# PARK_COUNTER_PT1_1.net
KiCad netlist of a schematic drawn in Altium Designer
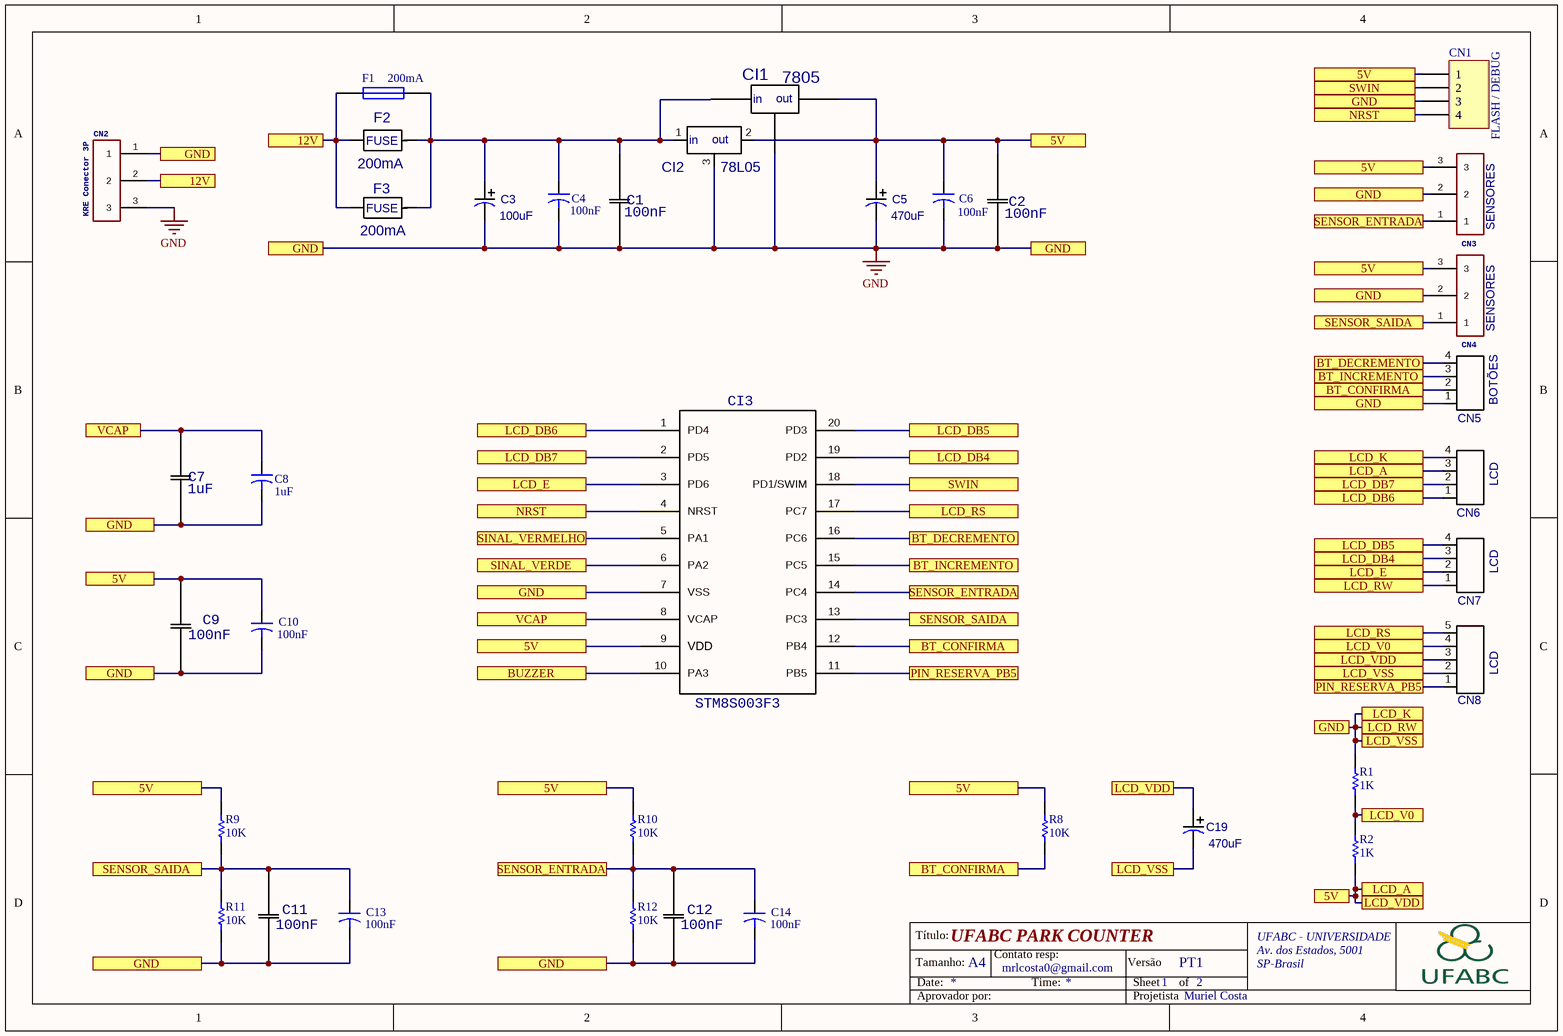
[diagram p0: PARK_COUNTER_PT1_1.SchDoc]

(export (version "E")
  (design (tool "Eeschema 10.0.6"))
  (components
    (comp (ref "C1")
      (value "100nF")
      (footprint "C0603")
      (description "Capacitor")
      (fields (field (name "Comment") "C0603"))
      (libsource (lib "SMD") (part "C0603"))
    )
    (comp (ref "C2")
      (value "100nF")
      (footprint "C0603")
      (description "Capacitor")
      (fields (field (name "Comment") "C0603"))
      (libsource (lib "SMD") (part "C0603"))
    )
    (comp (ref "C3")
      (value "100uF")
      (footprint "C_ELET_D8P5/3.5")
      (fields (field (name "Comment") "C_ELET_D8P5_35"))
      (libsource (lib "PTH") (part "C_ELET_D8P5_35"))
    )
    (comp (ref "C4")
      (value "100nF")
      (footprint "CAPR5-4X5")
      (description "Capacitor")
      (fields (field (name "Comment") "Cap2") (field (name "PUBLISHER") "Altium Limited"))
      (libsource (lib "Miscellaneous Devices") (part "Cap2"))
    )
    (comp (ref "C5")
      (value "470uF")
      (footprint "C_ELET_D8P5/3.5")
      (fields (field (name "Comment") "C_ELET_D8P5_35"))
      (libsource (lib "PTH") (part "C_ELET_D8P5_35"))
    )
    (comp (ref "C6")
      (value "100nF")
      (footprint "CAPR5-4X5")
      (description "Capacitor")
      (fields (field (name "Comment") "Cap2") (field (name "PUBLISHER") "Altium Limited"))
      (libsource (lib "Miscellaneous Devices") (part "Cap2"))
    )
    (comp (ref "C7")
      (value "1uF")
      (footprint "C0603")
      (description "Capacitor")
      (fields (field (name "Comment") "C0603"))
      (libsource (lib "SMD") (part "C0603"))
    )
    (comp (ref "C8")
      (value "1uF")
      (footprint "CAPR5-4X5")
      (description "Capacitor")
      (fields (field (name "Comment") "Cap2") (field (name "PUBLISHER") "Altium Limited"))
      (libsource (lib "Miscellaneous Devices") (part "Cap2"))
    )
    (comp (ref "C9")
      (value "100nF")
      (footprint "C0603")
      (description "Capacitor")
      (fields (field (name "Comment") "C0603"))
      (libsource (lib "SMD") (part "C0603"))
    )
    (comp (ref "C10")
      (value "100nF")
      (footprint "CAPR5-4X5")
      (description "Capacitor")
      (fields (field (name "Comment") "Cap2") (field (name "PUBLISHER") "Altium Limited"))
      (libsource (lib "Miscellaneous Devices") (part "Cap2"))
    )
    (comp (ref "C11")
      (value "100nF")
      (footprint "C0603")
      (description "Capacitor")
      (fields (field (name "Comment") "C0603"))
      (libsource (lib "SMD") (part "C0603"))
    )
    (comp (ref "C12")
      (value "100nF")
      (footprint "C0603")
      (description "Capacitor")
      (fields (field (name "Comment") "C0603"))
      (libsource (lib "SMD") (part "C0603"))
    )
    (comp (ref "C13")
      (value "100nF")
      (footprint "CAPR5-4X5")
      (description "Capacitor")
      (fields (field (name "Comment") "Cap2") (field (name "PUBLISHER") "Altium Limited"))
      (libsource (lib "Miscellaneous Devices") (part "Cap2"))
    )
    (comp (ref "C14")
      (value "100nF")
      (footprint "CAPR5-4X5")
      (description "Capacitor")
      (fields (field (name "Comment") "Cap2") (field (name "PUBLISHER") "Altium Limited"))
      (libsource (lib "Miscellaneous Devices") (part "Cap2"))
    )
    (comp (ref "C19")
      (value "470uF")
      (footprint "C_ELET_D8P5/3.5")
      (fields (field (name "Comment") "C_ELET_D8P5_35"))
      (libsource (lib "PTH") (part "C_ELET_D8P5_35"))
    )
    (comp (ref "CI1")
      (value "7805")
      (footprint "CI_7805_TO220_V")
      (fields (field (name "PART NUMBER") "004.02.00002"))
      (libsource (lib "PTH") (part "CI_7805_TO220_V"))
    )
    (comp (ref "CI2")
      (value "78L05")
      (footprint "TO92_78L05")
      (description "Glass Zener Diode, 500 Milliwatt")
      (fields (field (name "PART NUMBER") "004.02.00003"))
      (libsource (lib "PTH") (part "CI_78L05_TO92"))
    )
    (comp (ref "CI3")
      (value "STM8S003F3")
      (footprint "TSSOP20")
      (fields (field (name "PART NUMBER") "004.07.00026") (field (name "Comment") "CI_STM8S003F3_TSSOP20"))
      (libsource (lib "SMD") (part "CI_STM8S003F3_TSSOP20"))
    )
    (comp (ref "CN1")
      (value "FLASH / DEBUG")
      (footprint "HDR1X4")
      (description "Header, 4-Pin")
      (fields (field (name "PUBLISHER") "Altium Limited"))
      (libsource (lib "Miscellaneous Connectors") (part "Header 4"))
    )
    (comp (ref "CN2") (value "KRE Conector 3P") (footprint "KRE-3P") (libsource (lib "kre") (part "KRE-3P")))
    (comp (ref "CN3") (value "SENSORES") (footprint "KRE-3P") (libsource (lib "kre") (part "KRE-3P")))
    (comp (ref "CN4") (value "SENSORES") (footprint "KRE-3P") (libsource (lib "kre") (part "KRE-3P")))
    (comp (ref "CN5")
      (value "BOTÕES")
      (footprint "CON_BP1X4_180")
      (description "Capacitor")
      (fields (field (name "Comment") "CON_BP1X4_180"))
      (libsource (lib "CONECTORES") (part "CON_BP1X4_180"))
    )
    (comp (ref "CN6")
      (value "LCD")
      (footprint "CON_BP1X4_180")
      (description "Capacitor")
      (fields (field (name "Comment") "CON_BP1X4_180"))
      (libsource (lib "CONECTORES") (part "CON_BP1X4_180"))
    )
    (comp (ref "CN7")
      (value "LCD")
      (footprint "CON_BP1X4_180")
      (description "Capacitor")
      (fields (field (name "Comment") "CON_BP1X4_180"))
      (libsource (lib "CONECTORES") (part "CON_BP1X4_180"))
    )
    (comp (ref "CN8")
      (value "LCD")
      (footprint "CON_BP1X5_180")
      (fields (field (name "Comment") "CON_BP1X5_180"))
      (libsource (lib "CONECTORES") (part "CON_BP1X5_180"))
    )
    (comp (ref "F1")
      (value "200mA")
      (footprint "PIN-W2/E2.8")
      (description "Fuse")
      (fields (field (name "PUBLISHER") "Altium Limited"))
      (libsource (lib "Miscellaneous Devices") (part "Fuse 1"))
    )
    (comp (ref "F2")
      (value "200mA")
      (footprint "MINI_FUSE_BOARD_GLASS")
      (fields (field (name "Comment") "MINI_FUSE_BOARD_GLASS"))
      (libsource (lib "PTH") (part "fuse_board_glass"))
    )
    (comp (ref "F3")
      (value "200mA")
      (footprint "fuse_board_suporte")
      (fields (field (name "Comment") "MINI_FUSE_BOARD_SUP_GLASS"))
      (libsource (lib "PTH") (part "fuse_board_suporte"))
    )
    (comp (ref "R1")
      (value "1K")
      (footprint "AXIAL-0.3")
      (description "Resistor")
      (fields (field (name "Comment") "Res1") (field (name "PUBLISHER") "Altium Limited"))
      (libsource (lib "Miscellaneous Devices") (part "Res1"))
    )
    (comp (ref "R2")
      (value "1K")
      (footprint "AXIAL-0.3")
      (description "Resistor")
      (fields (field (name "Comment") "Res1") (field (name "PUBLISHER") "Altium Limited"))
      (libsource (lib "Miscellaneous Devices") (part "Res1"))
    )
    (comp (ref "R8")
      (value "10K")
      (footprint "AXIAL-0.3")
      (description "Resistor")
      (fields (field (name "Comment") "Res1") (field (name "PUBLISHER") "Altium Limited"))
      (libsource (lib "Miscellaneous Devices") (part "Res1"))
    )
    (comp (ref "R9")
      (value "10K")
      (footprint "AXIAL-0.3")
      (description "Resistor")
      (fields (field (name "Comment") "Res1") (field (name "PUBLISHER") "Altium Limited"))
      (libsource (lib "Miscellaneous Devices") (part "Res1"))
    )
    (comp (ref "R10")
      (value "10K")
      (footprint "AXIAL-0.3")
      (description "Resistor")
      (fields (field (name "Comment") "Res1") (field (name "PUBLISHER") "Altium Limited"))
      (libsource (lib "Miscellaneous Devices") (part "Res1"))
    )
    (comp (ref "R11")
      (value "10K")
      (footprint "AXIAL-0.3")
      (description "Resistor")
      (fields (field (name "Comment") "Res1") (field (name "PUBLISHER") "Altium Limited"))
      (libsource (lib "Miscellaneous Devices") (part "Res1"))
    )
    (comp (ref "R12")
      (value "10K")
      (footprint "AXIAL-0.3")
      (description "Resistor")
      (fields (field (name "Comment") "Res1") (field (name "PUBLISHER") "Altium Limited"))
      (libsource (lib "Miscellaneous Devices") (part "Res1"))
    )
  )
  (nets
    (net (code "1") (name "/5V") (class "Default")
      (node (ref "C10") (pin "1") (pinfunction "1_1") (pintype "passive"))
      (node (ref "C19") (pin "2") (pinfunction "2_2") (pintype "passive"))
      (node (ref "C2") (pin "2") (pinfunction "2_2") (pintype "passive"))
      (node (ref "C5") (pin "2") (pinfunction "2_2") (pintype "passive"))
      (node (ref "C6") (pin "1") (pinfunction "1_1") (pintype "passive"))
      (node (ref "C9") (pin "2") (pinfunction "2_2") (pintype "passive"))
      (node (ref "CI1") (pin "2") (pintype "passive"))
      (node (ref "CI2") (pin "2") (pinfunction "out_2") (pintype "passive"))
      (node (ref "CI3") (pin "9") (pinfunction "VDD_9") (pintype "passive"))
      (node (ref "CN1") (pin "1") (pinfunction "1_1") (pintype "passive"))
      (node (ref "CN3") (pin "3") (pinfunction "3_3") (pintype "passive"))
      (node (ref "CN4") (pin "3") (pinfunction "3_3") (pintype "passive"))
      (node (ref "CN6") (pin "3") (pintype "passive"))
      (node (ref "CN8") (pin "3") (pintype "passive"))
      (node (ref "R10") (pin "2") (pinfunction "2_2") (pintype "passive"))
      (node (ref "R2") (pin "1") (pinfunction "1_1") (pintype "passive"))
      (node (ref "R8") (pin "2") (pinfunction "2_2") (pintype "passive"))
      (node (ref "R9") (pin "2") (pinfunction "2_2") (pintype "passive"))
    )
    (net (code "2") (name "/12V") (class "Default")
      (node (ref "CN2") (pin "2") (pinfunction "2_2") (pintype "passive"))
      (node (ref "F1") (pin "1") (pinfunction "1_1") (pintype "passive"))
      (node (ref "F2") (pin "2") (pintype "passive"))
      (node (ref "F3") (pin "2") (pintype "passive"))
    )
    (net (code "3") (name "/BT_CONFIRMA") (class "Default")
      (node (ref "CI3") (pin "12") (pinfunction "PB4_12") (pintype "passive"))
      (node (ref "CN5") (pin "2") (pintype "passive"))
      (node (ref "R8") (pin "1") (pinfunction "1_1") (pintype "passive"))
    )
    (net (code "4") (name "/BT_DECREMENTO") (class "Default")
      (node (ref "CI3") (pin "16") (pinfunction "PC6_16") (pintype "passive"))
      (node (ref "CN5") (pin "4") (pintype "passive"))
    )
    (net (code "5") (name "/BT_INCREMENTO") (class "Default")
      (node (ref "CI3") (pin "15") (pinfunction "PC5_15") (pintype "passive"))
      (node (ref "CN5") (pin "3") (pintype "passive"))
    )
    (net (code "6") (name "/BUZZER") (class "Default")
      (node (ref "CI3") (pin "10") (pinfunction "PA3_10") (pintype "passive"))
    )
    (net (code "7") (name "/LCD_DB4") (class "Default")
      (node (ref "CI3") (pin "19") (pinfunction "PD2_19") (pintype "passive"))
      (node (ref "CN7") (pin "3") (pintype "passive"))
    )
    (net (code "8") (name "/LCD_DB5") (class "Default")
      (node (ref "CI3") (pin "20") (pinfunction "PD3_20") (pintype "passive"))
      (node (ref "CN7") (pin "4") (pintype "passive"))
    )
    (net (code "9") (name "/LCD_DB6") (class "Default")
      (node (ref "CI3") (pin "1") (pinfunction "PD4_1") (pintype "passive"))
      (node (ref "CN6") (pin "1") (pintype "passive"))
    )
    (net (code "10") (name "/LCD_DB7") (class "Default")
      (node (ref "CI3") (pin "2") (pinfunction "PD5_2") (pintype "passive"))
      (node (ref "CN6") (pin "2") (pintype "passive"))
    )
    (net (code "11") (name "/LCD_E") (class "Default")
      (node (ref "CI3") (pin "3") (pinfunction "PD6_3") (pintype "passive"))
      (node (ref "CN7") (pin "2") (pintype "passive"))
    )
    (net (code "12") (name "/LCD_RS") (class "Default")
      (node (ref "CI3") (pin "17") (pinfunction "PC7_17") (pintype "passive"))
      (node (ref "CN8") (pin "5") (pintype "passive"))
    )
    (net (code "13") (name "/LCD_V0") (class "Default")
      (node (ref "CN8") (pin "4") (pintype "passive"))
      (node (ref "R1") (pin "1") (pinfunction "1_1") (pintype "passive"))
      (node (ref "R2") (pin "2") (pinfunction "2_2") (pintype "passive"))
    )
    (net (code "14") (name "/NRST") (class "Default")
      (node (ref "CI3") (pin "4") (pinfunction "NRST_4") (pintype "passive"))
      (node (ref "CN1") (pin "4") (pinfunction "4_4") (pintype "passive"))
    )
    (net (code "15") (name "/PIN_RESERVA_PB5") (class "Default")
      (node (ref "CI3") (pin "11") (pinfunction "PB5_11") (pintype "passive"))
      (node (ref "CN8") (pin "1") (pintype "passive"))
    )
    (net (code "16") (name "/SENSOR_ENTRADA") (class "Default")
      (node (ref "C12") (pin "2") (pinfunction "2_2") (pintype "passive"))
      (node (ref "C14") (pin "1") (pinfunction "1_1") (pintype "passive"))
      (node (ref "CI3") (pin "14") (pinfunction "PC4_14") (pintype "passive"))
      (node (ref "CN3") (pin "1") (pinfunction "1_1") (pintype "passive"))
      (node (ref "R10") (pin "1") (pinfunction "1_1") (pintype "passive"))
      (node (ref "R12") (pin "2") (pinfunction "2_2") (pintype "passive"))
    )
    (net (code "17") (name "/SENSOR_SAIDA") (class "Default")
      (node (ref "C11") (pin "2") (pinfunction "2_2") (pintype "passive"))
      (node (ref "C13") (pin "1") (pinfunction "1_1") (pintype "passive"))
      (node (ref "CI3") (pin "13") (pinfunction "PC3_13") (pintype "passive"))
      (node (ref "CN4") (pin "1") (pinfunction "1_1") (pintype "passive"))
      (node (ref "R11") (pin "2") (pinfunction "2_2") (pintype "passive"))
      (node (ref "R9") (pin "1") (pinfunction "1_1") (pintype "passive"))
    )
    (net (code "18") (name "/SINAL_VERDE") (class "Default")
      (node (ref "CI3") (pin "6") (pinfunction "PA2_6") (pintype "passive"))
    )
    (net (code "19") (name "/SINAL_VERMELHO") (class "Default")
      (node (ref "CI3") (pin "5") (pinfunction "PA1_5") (pintype "passive"))
    )
    (net (code "20") (name "/SWIN") (class "Default")
      (node (ref "CI3") (pin "18") (pinfunction "PD1/SWIM_18") (pintype "passive"))
      (node (ref "CN1") (pin "2") (pinfunction "2_2") (pintype "passive"))
    )
    (net (code "21") (name "/VCAP") (class "Default")
      (node (ref "C7") (pin "2") (pinfunction "2_2") (pintype "passive"))
      (node (ref "C8") (pin "1") (pinfunction "1_1") (pintype "passive"))
      (node (ref "CI3") (pin "8") (pinfunction "VCAP_8") (pintype "passive"))
    )
    (net (code "22") (name "GND") (class "Default")
      (node (ref "C1") (pin "1") (pinfunction "1_1") (pintype "passive"))
      (node (ref "C10") (pin "2") (pinfunction "2_2") (pintype "passive"))
      (node (ref "C11") (pin "1") (pinfunction "1_1") (pintype "passive"))
      (node (ref "C12") (pin "1") (pinfunction "1_1") (pintype "passive"))
      (node (ref "C13") (pin "2") (pinfunction "2_2") (pintype "passive"))
      (node (ref "C14") (pin "2") (pinfunction "2_2") (pintype "passive"))
      (node (ref "C19") (pin "1") (pinfunction "1_1") (pintype "passive"))
      (node (ref "C2") (pin "1") (pinfunction "1_1") (pintype "passive"))
      (node (ref "C3") (pin "1") (pinfunction "1_1") (pintype "passive"))
      (node (ref "C4") (pin "2") (pinfunction "2_2") (pintype "passive"))
      (node (ref "C5") (pin "1") (pinfunction "1_1") (pintype "passive"))
      (node (ref "C6") (pin "2") (pinfunction "2_2") (pintype "passive"))
      (node (ref "C7") (pin "1") (pinfunction "1_1") (pintype "passive"))
      (node (ref "C8") (pin "2") (pinfunction "2_2") (pintype "passive"))
      (node (ref "C9") (pin "1") (pinfunction "1_1") (pintype "passive"))
      (node (ref "CI1") (pin "3") (pintype "passive"))
      (node (ref "CI2") (pin "3") (pinfunction "gnd_3") (pintype "passive"))
      (node (ref "CI3") (pin "7") (pinfunction "VSS_7") (pintype "passive"))
      (node (ref "CN1") (pin "3") (pinfunction "3_3") (pintype "passive"))
      (node (ref "CN2") (pin "1") (pinfunction "1_1") (pintype "passive"))
      (node (ref "CN2") (pin "3") (pinfunction "3_3") (pintype "passive"))
      (node (ref "CN3") (pin "2") (pinfunction "2_2") (pintype "passive"))
      (node (ref "CN4") (pin "2") (pinfunction "2_2") (pintype "passive"))
      (node (ref "CN5") (pin "1") (pintype "passive"))
      (node (ref "CN6") (pin "4") (pintype "passive"))
      (node (ref "CN7") (pin "1") (pintype "passive"))
      (node (ref "CN8") (pin "2") (pintype "passive"))
      (node (ref "R1") (pin "2") (pinfunction "2_2") (pintype "passive"))
      (node (ref "R11") (pin "1") (pinfunction "1_1") (pintype "passive"))
      (node (ref "R12") (pin "1") (pinfunction "1_1") (pintype "passive"))
    )
    (net (code "23") (name "Net-(CI2-in)") (class "Default")
      (node (ref "C1") (pin "2") (pinfunction "2_2") (pintype "passive"))
      (node (ref "C3") (pin "2") (pinfunction "2_2") (pintype "passive"))
      (node (ref "C4") (pin "1") (pinfunction "1_1") (pintype "passive"))
      (node (ref "CI1") (pin "1") (pintype "passive"))
      (node (ref "CI2") (pin "1") (pinfunction "in_1") (pintype "passive"))
      (node (ref "F1") (pin "2") (pinfunction "2_2") (pintype "passive"))
      (node (ref "F2") (pin "1") (pintype "passive"))
      (node (ref "F3") (pin "1") (pintype "passive"))
    )
    (net (code "24") (name "unconnected-(C3-Pad3)") (class "Default")
      (node (ref "C3") (pin "3") (pintype "passive"))
    )
    (net (code "25") (name "unconnected-(C5-Pad3)") (class "Default")
      (node (ref "C5") (pin "3") (pintype "passive"))
    )
    (net (code "26") (name "unconnected-(C19-Pad3)") (class "Default")
      (node (ref "C19") (pin "3") (pintype "passive"))
    )
    (net (code "27") (name "unconnected-(F2-Pad3)") (class "Default")
      (node (ref "F2") (pin "3") (pintype "passive"))
    )
    (net (code "28") (name "unconnected-(F2-Pad4)") (class "Default")
      (node (ref "F2") (pin "4") (pintype "passive"))
    )
    (net (code "29") (name "unconnected-(F3-Pad3)") (class "Default")
      (node (ref "F3") (pin "3") (pintype "passive"))
    )
    (net (code "30") (name "unconnected-(F3-Pad4)") (class "Default")
      (node (ref "F3") (pin "4") (pintype "passive"))
    )
  )
)
